# utilidong-septic-sepic-lt1610-mk-1_0.net
KiCad netlist of a schematic drawn in EAGLE
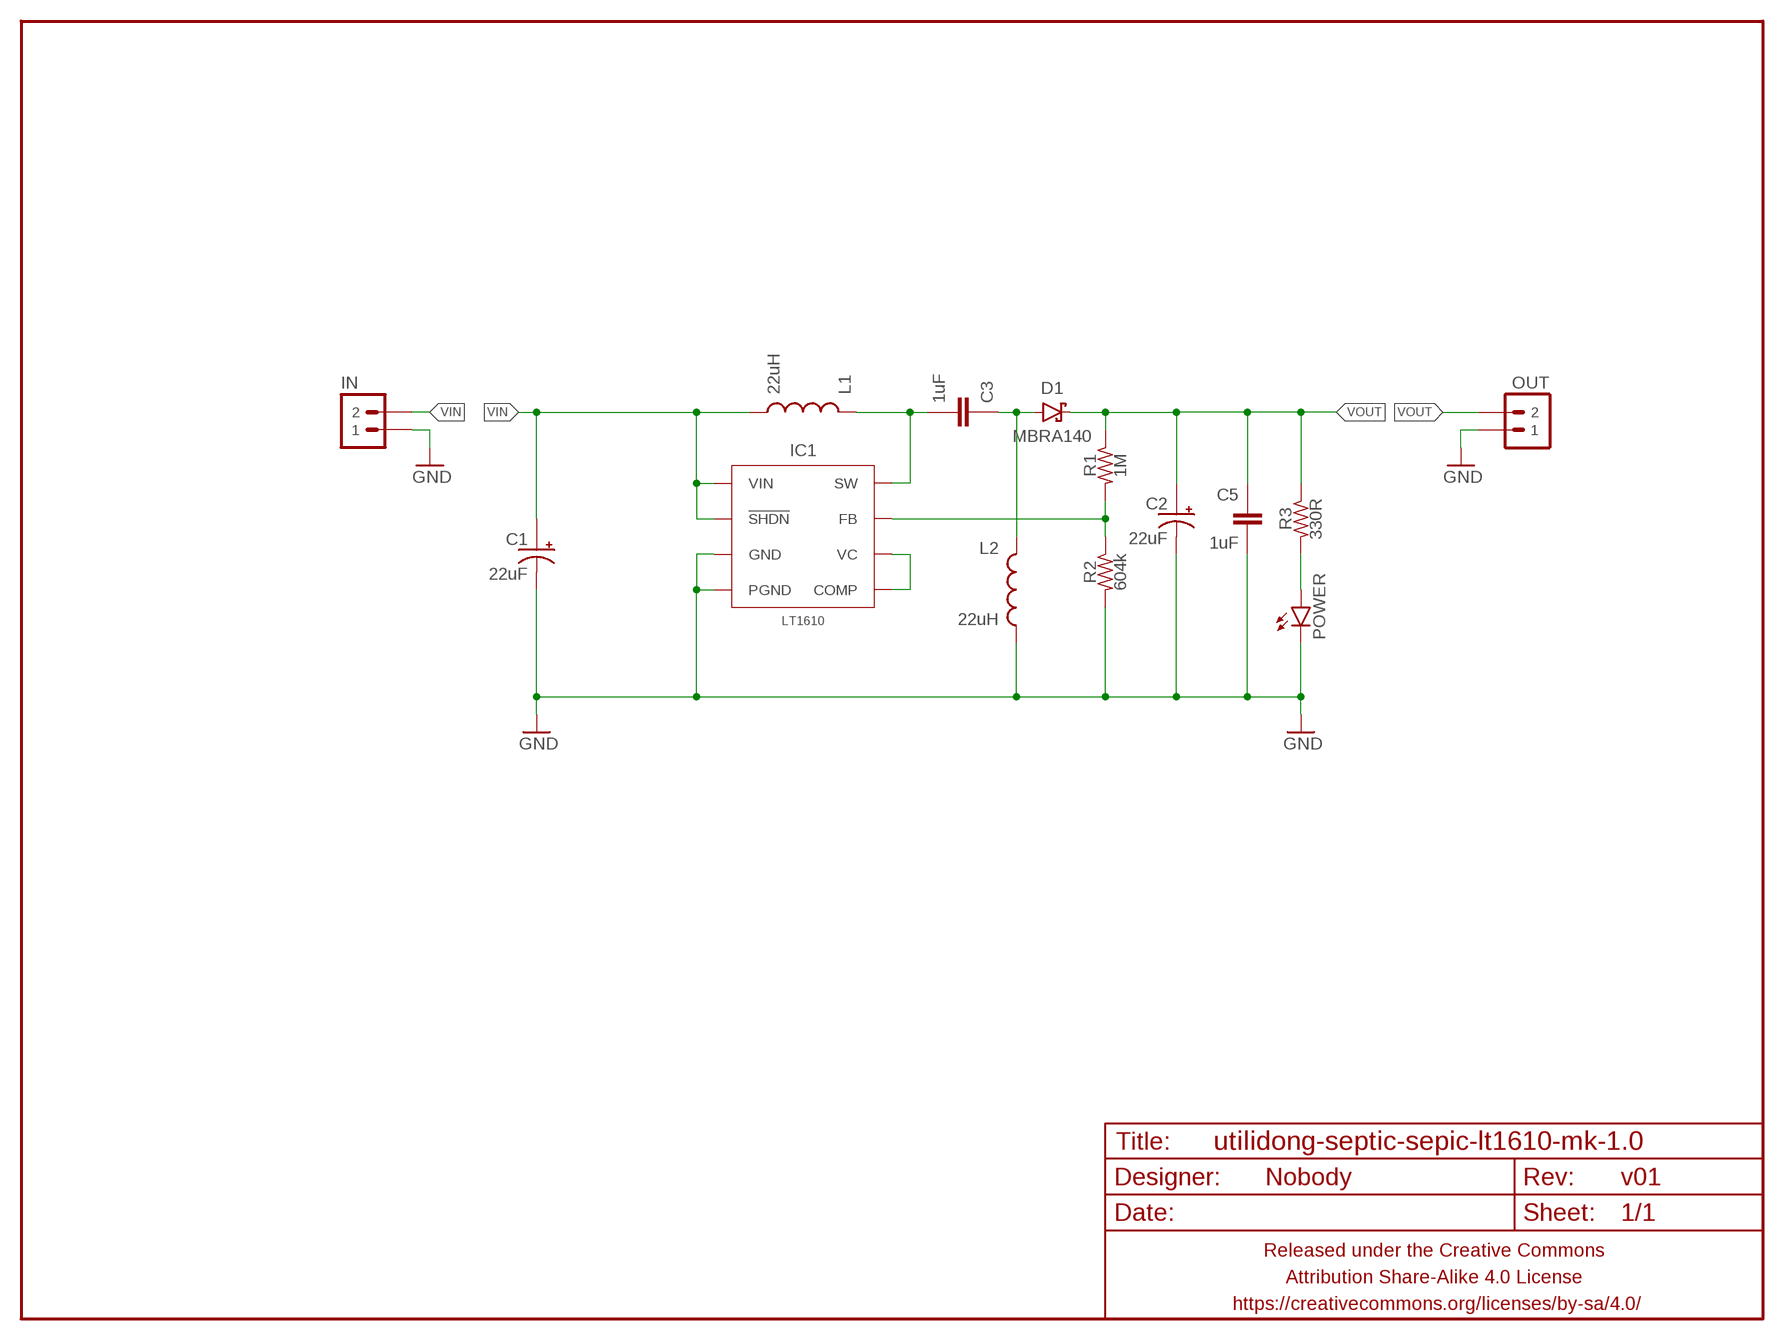
[diagram p0: schematic, sheet 1]

(export (version "E")
  (design (tool "Eeschema 10.0.6"))
  (components
    (comp (ref "C1")
      (value "22uF")
      (footprint "eagle-import:E2,5-6")
      (libsource (lib "eagle-import") (part "CAPACITOR-POLARIZEDE2.5-6"))
    )
    (comp (ref "C2")
      (value "22uF")
      (footprint "eagle-import:E2,5-6")
      (libsource (lib "eagle-import") (part "CAPACITOR-POLARIZEDE2.5-6"))
    )
    (comp (ref "C3")
      (value "1uF")
      (footprint "eagle-import:C0805")
      (libsource (lib "eagle-import") (part "CAPACITOR-CERAMICC0805"))
    )
    (comp (ref "C5")
      (value "1uF")
      (footprint "eagle-import:C0805")
      (libsource (lib "eagle-import") (part "CAPACITOR-CERAMICC0805"))
    )
    (comp (ref "D1")
      (value "MBRA140")
      (footprint "eagle-import:SMA-DIODE-SCHOTTKY")
      (libsource (lib "eagle-import") (part "DIODE-SCHOTTKYSMA"))
    )
    (comp (ref "FRAME1")
      (value "FRAME-LETTERNO_PACKAGE")
      (footprint "eagle-import:DUMMY")
      (fields (field (name "DESIGNER") "Nobody"))
      (libsource (lib "eagle-import") (part "FRAME-LETTERNO_PACKAGE"))
    )
    (comp (ref "IC1")
      (value "LT1610")
      (footprint "eagle-import:SO08")
      (libsource (lib "eagle-import") (part "LT1610SOICN8"))
    )
    (comp (ref "IN")
      (value "M02PTH-CENTERED-R+")
      (footprint "eagle-import:1X02-CENTER-R+")
      (libsource (lib "eagle-import") (part "M02PTH-CENTERED-R+"))
    )
    (comp (ref "L1")
      (value "22uH")
      (footprint "eagle-import:TAIYO-YUDEN-40XX")
      (libsource (lib "eagle-import") (part "INDUCTORTAIYO-YUDEN-40XX"))
    )
    (comp (ref "L2")
      (value "22uH")
      (footprint "eagle-import:TAIYO-YUDEN-40XX")
      (libsource (lib "eagle-import") (part "INDUCTORTAIYO-YUDEN-40XX"))
    )
    (comp (ref "OUT")
      (value "M02PTH-CENTERED-R+")
      (footprint "eagle-import:1X02-CENTER-R+")
      (libsource (lib "eagle-import") (part "M02PTH-CENTERED-R+"))
    )
    (comp (ref "POWER")
      (value "LED1206")
      (footprint "eagle-import:LED-1206")
      (libsource (lib "eagle-import") (part "LED1206"))
    )
    (comp (ref "R1")
      (value "1M")
      (footprint "eagle-import:R0805")
      (libsource (lib "eagle-import") (part "RESISTORR0805"))
    )
    (comp (ref "R2")
      (value "604k")
      (footprint "eagle-import:R0805")
      (libsource (lib "eagle-import") (part "RESISTORR0805"))
    )
    (comp (ref "R3")
      (value "330R")
      (footprint "eagle-import:R0805")
      (libsource (lib "eagle-import") (part "RESISTORR0805"))
    )
  )
  (nets
    (net (code "1") (name "GND") (class "Default")
      (node (ref "C1") (pin "-") (pinfunction "-_-") (pintype "passive"))
      (node (ref "C2") (pin "-") (pinfunction "-_-") (pintype "passive"))
      (node (ref "C5") (pin "2") (pinfunction "2_2") (pintype "passive"))
      (node (ref "IC1") (pin "4") (pinfunction "PGND_4") (pintype "passive"))
      (node (ref "IC1") (pin "7") (pinfunction "GND_7") (pintype "passive"))
      (node (ref "IN") (pin "1") (pinfunction "1_1") (pintype "passive"))
      (node (ref "L2") (pin "2") (pinfunction "2_2") (pintype "passive"))
      (node (ref "OUT") (pin "1") (pinfunction "1_1") (pintype "passive"))
      (node (ref "POWER") (pin "C") (pinfunction "C_C") (pintype "passive"))
      (node (ref "R2") (pin "2") (pinfunction "2_2") (pintype "passive"))
    )
    (net (code "2") (name "Net-(C3-Pad1)") (class "Default")
      (node (ref "C3") (pin "1") (pinfunction "1_1") (pintype "passive"))
      (node (ref "D1") (pin "A") (pinfunction "A_A") (pintype "passive"))
      (node (ref "L2") (pin "1") (pinfunction "1_1") (pintype "passive"))
    )
    (net (code "3") (name "Net-(IC1-COMP)") (class "Default")
      (node (ref "IC1") (pin "1") (pinfunction "VC_1") (pintype "passive"))
      (node (ref "IC1") (pin "8") (pinfunction "COMP_8") (pintype "passive"))
    )
    (net (code "4") (name "Net-(IC1-FB)") (class "Default")
      (node (ref "IC1") (pin "2") (pinfunction "FB_2") (pintype "passive"))
      (node (ref "R1") (pin "2") (pinfunction "2_2") (pintype "passive"))
      (node (ref "R2") (pin "1") (pinfunction "1_1") (pintype "passive"))
    )
    (net (code "5") (name "Net-(IC1-SW)") (class "Default")
      (node (ref "C3") (pin "2") (pinfunction "2_2") (pintype "passive"))
      (node (ref "IC1") (pin "5") (pinfunction "SW_5") (pintype "passive"))
      (node (ref "L1") (pin "1") (pinfunction "1_1") (pintype "passive"))
    )
    (net (code "6") (name "Net-(POWER-PadA)") (class "Default")
      (node (ref "POWER") (pin "A") (pinfunction "A_A") (pintype "passive"))
      (node (ref "R3") (pin "2") (pinfunction "2_2") (pintype "passive"))
    )
    (net (code "7") (name "VIN") (class "Default")
      (node (ref "C1") (pin "+") (pinfunction "+_+") (pintype "passive"))
      (node (ref "IC1") (pin "3") (pinfunction "~{SHDN}_3") (pintype "passive"))
      (node (ref "IC1") (pin "6") (pinfunction "VIN_6") (pintype "passive"))
      (node (ref "IN") (pin "2") (pinfunction "2_2") (pintype "passive"))
      (node (ref "L1") (pin "2") (pinfunction "2_2") (pintype "passive"))
    )
    (net (code "8") (name "VOUT") (class "Default")
      (node (ref "C2") (pin "+") (pinfunction "+_+") (pintype "passive"))
      (node (ref "C5") (pin "1") (pinfunction "1_1") (pintype "passive"))
      (node (ref "D1") (pin "C") (pinfunction "C_C") (pintype "passive"))
      (node (ref "OUT") (pin "2") (pinfunction "2_2") (pintype "passive"))
      (node (ref "R1") (pin "1") (pinfunction "1_1") (pintype "passive"))
      (node (ref "R3") (pin "1") (pinfunction "1_1") (pintype "passive"))
    )
  )
)
